# PV_MCU_IO.net
KiCad netlist of a schematic drawn in Altium Designer
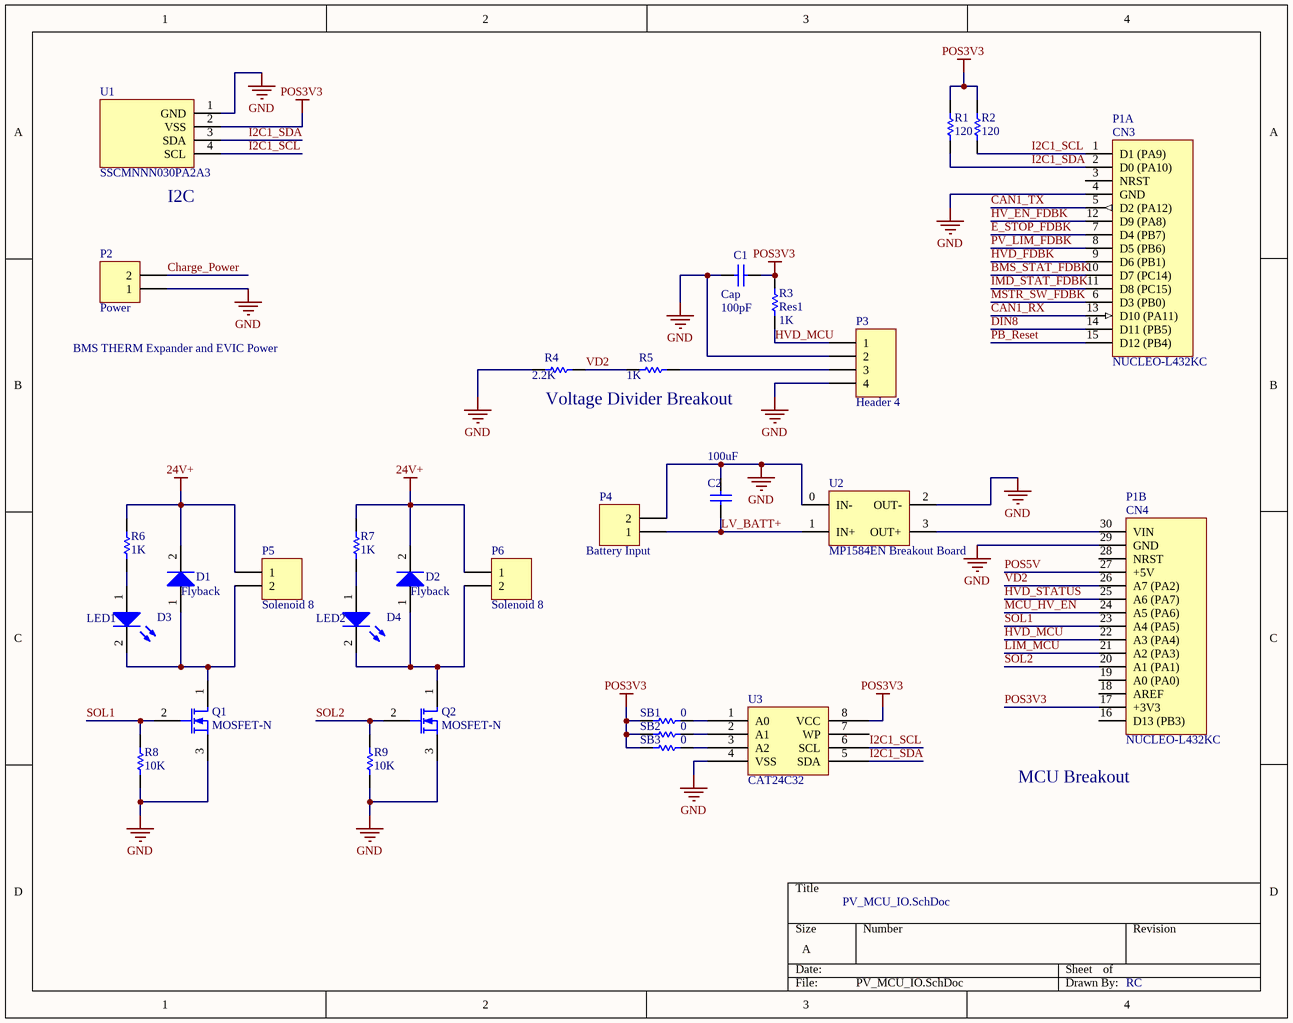
[diagram p0: PV_MCU_IO.SchDoc]

(export (version "E")
  (design (tool "Eeschema 10.0.6"))
  (components
    (comp (ref "C1")
      (value "Cap")
      (footprint "1206")
      (description "Capacitor")
      (fields (field (name "ALTIUM_VALUE") "100pF") (field (name "PUBLISHER") "Altium Limited"))
      (libsource (lib "Miscellaneous Devices") (part "Cap"))
    )
    (comp (ref "C2")
      (value "100uF")
      (footprint "CAPR5-4X5")
      (description "Capacitor")
      (fields (field (name "Comment") "Cap") (field (name "PUBLISHER") "Altium Limited"))
      (libsource (lib "Miscellaneous Devices") (part "Cap"))
    )
    (comp (ref "D1")
      (value "Flyback")
      (footprint "1N4007")
      (description "Default Diode")
      (fields (field (name "PUBLISHER") "Altium Limited"))
      (libsource (lib "Miscellaneous Devices") (part "Diode"))
    )
    (comp (ref "D2")
      (value "Flyback")
      (footprint "1N4007")
      (description "Default Diode")
      (fields (field (name "PUBLISHER") "Altium Limited"))
      (libsource (lib "Miscellaneous Devices") (part "Diode"))
    )
    (comp (ref "D3")
      (value "LED1")
      (footprint "1206 LED")
      (description "Typical RED, GREEN, YELLOW, AMBER GaAs LED")
      (fields (field (name "PUBLISHER") "Altium Limited"))
      (libsource (lib "Miscellaneous Devices") (part "LED2"))
    )
    (comp (ref "D4")
      (value "LED2")
      (footprint "1206 LED")
      (description "Typical RED, GREEN, YELLOW, AMBER GaAs LED")
      (fields (field (name "PUBLISHER") "Altium Limited"))
      (libsource (lib "Miscellaneous Devices") (part "LED2"))
    )
    (comp (ref "P1")
      (value "NUCLEO-L432KC")
      (footprint "NUCLEO-32")
      (description "STM32L432KC Development Board")
      (libsource (lib "") (part "NUCLEO-L432KC_1"))
    )
    (comp (ref "P2")
      (value "Power")
      (footprint "2POS TERM BLOCK")
      (description "Header, 2-Pin")
      (fields (field (name "PUBLISHER") "Altium Limited"))
      (libsource (lib "") (part "Header 2_1"))
    )
    (comp (ref "P3")
      (value "Header 4")
      (footprint "4POS TERM BLOCK")
      (description "Header, 4-Pin")
      (fields (field (name "PUBLISHER") "Altium Limited"))
      (libsource (lib "Miscellaneous Connectors") (part "Header 4"))
    )
    (comp (ref "P4")
      (value "Battery Input")
      (footprint "2POS TERM BLOCK")
      (description "Header, 2-Pin")
      (fields (field (name "PUBLISHER") "Altium Limited"))
      (libsource (lib "") (part "Header 2_1"))
    )
    (comp (ref "P5")
      (value "Solenoid 8")
      (footprint "2POS TERM BLOCK")
      (description "Header, 2-Pin")
      (fields (field (name "PUBLISHER") "Altium Limited"))
      (libsource (lib "Miscellaneous Connectors") (part "Header 2"))
    )
    (comp (ref "P6")
      (value "Solenoid 8")
      (footprint "2POS TERM BLOCK")
      (description "Header, 2-Pin")
      (fields (field (name "PUBLISHER") "Altium Limited"))
      (libsource (lib "Miscellaneous Connectors") (part "Header 2"))
    )
    (comp (ref "Q1")
      (value "MOSFET-N")
      (footprint "SOT-23-3")
      (description "N-Channel MOSFET")
      (fields (field (name "PUBLISHER") "Altium Limited"))
      (libsource (lib "Miscellaneous Devices") (part "MOSFET-N"))
    )
    (comp (ref "Q2")
      (value "MOSFET-N")
      (footprint "SOT-23-3")
      (description "N-Channel MOSFET")
      (fields (field (name "PUBLISHER") "Altium Limited"))
      (libsource (lib "Miscellaneous Devices") (part "MOSFET-N"))
    )
    (comp (ref "R1")
      (value "120")
      (footprint "1206")
      (description "Resistor")
      (fields (field (name "Comment") "Res1") (field (name "PUBLISHER") "Altium Limited"))
      (libsource (lib "Miscellaneous Devices") (part "Res1"))
    )
    (comp (ref "R2")
      (value "120")
      (footprint "1206")
      (description "Resistor")
      (fields (field (name "Comment") "Res1") (field (name "PUBLISHER") "Altium Limited"))
      (libsource (lib "Miscellaneous Devices") (part "Res1"))
    )
    (comp (ref "R3")
      (value "Res1")
      (footprint "1206")
      (description "Resistor")
      (fields (field (name "ALTIUM_VALUE") "1K") (field (name "PUBLISHER") "Altium Limited"))
      (libsource (lib "Miscellaneous Devices") (part "Res1"))
    )
    (comp (ref "R4")
      (value "2.2K")
      (footprint "1206")
      (description "Resistor")
      (fields (field (name "Comment") "Res1") (field (name "PUBLISHER") "Altium Limited"))
      (libsource (lib "Miscellaneous Devices") (part "Res1"))
    )
    (comp (ref "R5")
      (value "1K")
      (footprint "1206")
      (description "Resistor")
      (fields (field (name "Comment") "Res1") (field (name "PUBLISHER") "Altium Limited"))
      (libsource (lib "Miscellaneous Devices") (part "Res1"))
    )
    (comp (ref "R6")
      (value "1K")
      (footprint "1206")
      (description "Resistor")
      (fields (field (name "Comment") "Res1") (field (name "PUBLISHER") "Altium Limited"))
      (libsource (lib "Miscellaneous Devices") (part "Res1"))
    )
    (comp (ref "R7")
      (value "1K")
      (footprint "1206")
      (description "Resistor")
      (fields (field (name "Comment") "Res1") (field (name "PUBLISHER") "Altium Limited"))
      (libsource (lib "Miscellaneous Devices") (part "Res1"))
    )
    (comp (ref "R8")
      (value "10K")
      (footprint "1206")
      (description "Resistor")
      (fields (field (name "Comment") "Res1") (field (name "PUBLISHER") "Altium Limited"))
      (libsource (lib "Miscellaneous Devices") (part "Res1"))
    )
    (comp (ref "R9")
      (value "10K")
      (footprint "1206")
      (description "Resistor")
      (fields (field (name "Comment") "Res1") (field (name "PUBLISHER") "Altium Limited"))
      (libsource (lib "Miscellaneous Devices") (part "Res1"))
    )
    (comp (ref "SB1")
      (value "0")
      (footprint "6-0805_M")
      (description "Resistor")
      (fields (field (name "Comment") "Res1") (field (name "PUBLISHER") "Altium Limited"))
      (libsource (lib "Miscellaneous Devices") (part "Res1"))
    )
    (comp (ref "SB2")
      (value "0")
      (footprint "6-0805_M")
      (description "Resistor")
      (fields (field (name "Comment") "Res1") (field (name "PUBLISHER") "Altium Limited"))
      (libsource (lib "Miscellaneous Devices") (part "Res1"))
    )
    (comp (ref "SB3")
      (value "0")
      (footprint "6-0805_M")
      (description "Resistor")
      (fields (field (name "Comment") "Res1") (field (name "PUBLISHER") "Altium Limited"))
      (libsource (lib "Miscellaneous Devices") (part "Res1"))
    )
    (comp (ref "U1")
      (value "SSCMNNN030PA2A3")
      (footprint "8-SMT")
      (description "Honeywell Digital Pressure Sensor")
      (libsource (lib "ic") (part "SSCMNNN030PA2A3"))
    )
    (comp (ref "U2")
      (value "MP1584EN Breakout Board")
      (footprint "MP1584EN Breakout")
      (description "Buck Converter")
      (libsource (lib "ic") (part "MP1584EN Breakout Board"))
    )
    (comp (ref "U3")
      (value "CAT24C32")
      (footprint "SO8_N")
      (description "I2C EEPROM")
      (libsource (lib "ic") (part "CAT24C32"))
    )
  )
  (nets
    (net (code "1") (name "/BMS_STAT_FDBK") (class "Default")
      (node (ref "P1") (pin "10") (pinfunction "D7_(PC14)_10") (pintype "passive"))
    )
    (net (code "2") (name "/CAN1_RX") (class "Default")
      (node (ref "P1") (pin "13") (pinfunction "D10_(PA11)_13") (pintype "input"))
    )
    (net (code "3") (name "/CAN1_TX") (class "Default")
      (node (ref "P1") (pin "5") (pinfunction "D2_(PA12)_5") (pintype "output"))
    )
    (net (code "4") (name "/Charge_Power") (class "Default")
      (node (ref "P2") (pin "2") (pinfunction "2_2") (pintype "passive"))
    )
    (net (code "5") (name "/DIN8") (class "Default")
      (node (ref "P1") (pin "14") (pinfunction "D11_(PB5)_14") (pintype "passive"))
    )
    (net (code "6") (name "/E_STOP_FDBK") (class "Default")
      (node (ref "P1") (pin "7") (pinfunction "D4_(PB7)_7") (pintype "passive"))
    )
    (net (code "7") (name "/HVD_FDBK") (class "Default")
      (node (ref "P1") (pin "9") (pinfunction "D6_(PB1)_9") (pintype "passive"))
    )
    (net (code "8") (name "/HVD_MCU") (class "Default")
      (node (ref "P1") (pin "22") (pinfunction "A3_(PA4)_22") (pintype "passive"))
      (node (ref "P3") (pin "1") (pinfunction "1_1") (pintype "passive"))
      (node (ref "R3") (pin "1") (pinfunction "1_1") (pintype "passive"))
    )
    (net (code "9") (name "/HVD_STATUS") (class "Default")
      (node (ref "P1") (pin "25") (pinfunction "A6_(PA7)_25") (pintype "passive"))
    )
    (net (code "10") (name "/HV_EN_FDBK") (class "Default")
      (node (ref "P1") (pin "12") (pinfunction "D9_(PA8)_12") (pintype "passive"))
    )
    (net (code "11") (name "/I2C1_SCL") (class "Default")
      (node (ref "P1") (pin "1") (pinfunction "D1_(PA9)_1") (pintype "passive"))
      (node (ref "R2") (pin "1") (pinfunction "1_1") (pintype "passive"))
      (node (ref "U1") (pin "4") (pinfunction "SCL_4") (pintype "passive"))
      (node (ref "U3") (pin "6") (pinfunction "SCL_6") (pintype "passive"))
    )
    (net (code "12") (name "/I2C1_SDA") (class "Default")
      (node (ref "P1") (pin "2") (pinfunction "D0_(PA10)_2") (pintype "passive"))
      (node (ref "R1") (pin "1") (pinfunction "1_1") (pintype "passive"))
      (node (ref "U1") (pin "3") (pinfunction "SDA_3") (pintype "passive"))
      (node (ref "U3") (pin "5") (pinfunction "SDA_5") (pintype "passive"))
    )
    (net (code "13") (name "/IMD_STAT_FDBK") (class "Default")
      (node (ref "P1") (pin "11") (pinfunction "D8_(PC15)_11") (pintype "passive"))
    )
    (net (code "14") (name "/LIM_MCU") (class "Default")
      (node (ref "P1") (pin "21") (pinfunction "A2_(PA3)_21") (pintype "passive"))
    )
    (net (code "15") (name "/LV_BATT+") (class "Default")
      (node (ref "C2") (pin "1") (pinfunction "1_1") (pintype "passive"))
      (node (ref "P4") (pin "1") (pinfunction "1_1") (pintype "passive"))
      (node (ref "U2") (pin "1") (pinfunction "IN+_1") (pintype "power_in"))
    )
    (net (code "16") (name "/MCU_HV_EN") (class "Default")
      (node (ref "P1") (pin "24") (pinfunction "A5_(PA6)_24") (pintype "passive"))
    )
    (net (code "17") (name "/MSTR_SW_FDBK") (class "Default")
      (node (ref "P1") (pin "6") (pinfunction "D3_(PB0)_6") (pintype "passive"))
    )
    (net (code "18") (name "/PB_Reset") (class "Default")
      (node (ref "P1") (pin "15") (pinfunction "D12_(PB4)_15") (pintype "passive"))
    )
    (net (code "19") (name "/POS5V") (class "Default")
      (node (ref "P1") (pin "27") (pinfunction "+5V_27") (pintype "passive"))
    )
    (net (code "20") (name "/PV_LIM_FDBK") (class "Default")
      (node (ref "P1") (pin "8") (pinfunction "D5_(PB6)_8") (pintype "passive"))
    )
    (net (code "21") (name "/SOL1") (class "Default")
      (node (ref "P1") (pin "23") (pinfunction "A4_(PA5)_23") (pintype "passive"))
      (node (ref "Q1") (pin "2") (pinfunction "G_2") (pintype "passive"))
      (node (ref "R8") (pin "2") (pinfunction "2_2") (pintype "passive"))
    )
    (net (code "22") (name "/SOL2") (class "Default")
      (node (ref "P1") (pin "20") (pinfunction "A1_(PA1)_20") (pintype "passive"))
      (node (ref "Q2") (pin "2") (pinfunction "G_2") (pintype "passive"))
      (node (ref "R9") (pin "2") (pinfunction "2_2") (pintype "passive"))
    )
    (net (code "23") (name "/VD2") (class "Default")
      (node (ref "P1") (pin "26") (pinfunction "A7_(PA2)_26") (pintype "passive"))
      (node (ref "R4") (pin "2") (pinfunction "2_2") (pintype "passive"))
      (node (ref "R5") (pin "1") (pinfunction "1_1") (pintype "passive"))
    )
    (net (code "24") (name "24V+") (class "Default")
      (node (ref "D1") (pin "2") (pinfunction "K_2") (pintype "passive"))
      (node (ref "D2") (pin "2") (pinfunction "K_2") (pintype "passive"))
      (node (ref "P5") (pin "1") (pinfunction "1_1") (pintype "passive"))
      (node (ref "P6") (pin "1") (pinfunction "1_1") (pintype "passive"))
      (node (ref "R6") (pin "2") (pinfunction "2_2") (pintype "passive"))
      (node (ref "R7") (pin "2") (pinfunction "2_2") (pintype "passive"))
    )
    (net (code "25") (name "GND") (class "Default")
      (node (ref "C1") (pin "2") (pinfunction "2_2") (pintype "passive"))
      (node (ref "C2") (pin "2") (pinfunction "2_2") (pintype "passive"))
      (node (ref "P1") (pin "29") (pinfunction "GND_29") (pintype "passive"))
      (node (ref "P1") (pin "4") (pinfunction "GND_4") (pintype "passive"))
      (node (ref "P2") (pin "1") (pinfunction "1_1") (pintype "passive"))
      (node (ref "P3") (pin "2") (pinfunction "2_2") (pintype "passive"))
      (node (ref "P3") (pin "4") (pinfunction "4_4") (pintype "passive"))
      (node (ref "P4") (pin "2") (pinfunction "2_2") (pintype "passive"))
      (node (ref "Q1") (pin "3") (pinfunction "S_3") (pintype "passive"))
      (node (ref "Q2") (pin "3") (pinfunction "S_3") (pintype "passive"))
      (node (ref "R4") (pin "1") (pinfunction "1_1") (pintype "passive"))
      (node (ref "R8") (pin "1") (pinfunction "1_1") (pintype "passive"))
      (node (ref "R9") (pin "1") (pinfunction "1_1") (pintype "passive"))
      (node (ref "U1") (pin "1") (pinfunction "GND_1") (pintype "passive"))
      (node (ref "U2") (pin "0") (pinfunction "IN-_0") (pintype "passive"))
      (node (ref "U2") (pin "2") (pinfunction "OUT-_2") (pintype "passive"))
      (node (ref "U3") (pin "4") (pinfunction "VSS_4") (pintype "passive"))
    )
    (net (code "26") (name "Net-(D1-A)") (class "Default")
      (node (ref "D1") (pin "1") (pinfunction "A_1") (pintype "passive"))
      (node (ref "D3") (pin "2") (pinfunction "K_2") (pintype "passive"))
      (node (ref "P5") (pin "2") (pinfunction "2_2") (pintype "passive"))
      (node (ref "Q1") (pin "1") (pinfunction "D_1") (pintype "passive"))
    )
    (net (code "27") (name "Net-(D2-A)") (class "Default")
      (node (ref "D2") (pin "1") (pinfunction "A_1") (pintype "passive"))
      (node (ref "D4") (pin "2") (pinfunction "K_2") (pintype "passive"))
      (node (ref "P6") (pin "2") (pinfunction "2_2") (pintype "passive"))
      (node (ref "Q2") (pin "1") (pinfunction "D_1") (pintype "passive"))
    )
    (net (code "28") (name "Net-(D3-A)") (class "Default")
      (node (ref "D3") (pin "1") (pinfunction "A_1") (pintype "passive"))
      (node (ref "R6") (pin "1") (pinfunction "1_1") (pintype "passive"))
    )
    (net (code "29") (name "Net-(D4-A)") (class "Default")
      (node (ref "D4") (pin "1") (pinfunction "A_1") (pintype "passive"))
      (node (ref "R7") (pin "1") (pinfunction "1_1") (pintype "passive"))
    )
    (net (code "30") (name "Net-(P1B-VIN)") (class "Default")
      (node (ref "P1") (pin "30") (pinfunction "VIN_30") (pintype "passive"))
      (node (ref "U2") (pin "3") (pinfunction "OUT+_3") (pintype "power_in"))
    )
    (net (code "31") (name "Net-(P3-Pad3)") (class "Default")
      (node (ref "P3") (pin "3") (pinfunction "3_3") (pintype "passive"))
      (node (ref "R5") (pin "2") (pinfunction "2_2") (pintype "passive"))
    )
    (net (code "32") (name "Net-(U3-A0)") (class "Default")
      (node (ref "SB1") (pin "1") (pinfunction "1_1") (pintype "passive"))
      (node (ref "U3") (pin "1") (pinfunction "A0_1") (pintype "passive"))
    )
    (net (code "33") (name "Net-(U3-A1)") (class "Default")
      (node (ref "SB2") (pin "1") (pinfunction "1_1") (pintype "passive"))
      (node (ref "U3") (pin "2") (pinfunction "A1_2") (pintype "passive"))
    )
    (net (code "34") (name "Net-(U3-A2)") (class "Default")
      (node (ref "SB3") (pin "1") (pinfunction "1_1") (pintype "passive"))
      (node (ref "U3") (pin "3") (pinfunction "A2_3") (pintype "passive"))
    )
    (net (code "35") (name "POS3V3") (class "Default")
      (node (ref "C1") (pin "1") (pinfunction "1_1") (pintype "passive"))
      (node (ref "P1") (pin "17") (pinfunction "+3V3_17") (pintype "passive"))
      (node (ref "R1") (pin "2") (pinfunction "2_2") (pintype "passive"))
      (node (ref "R2") (pin "2") (pinfunction "2_2") (pintype "passive"))
      (node (ref "R3") (pin "2") (pinfunction "2_2") (pintype "passive"))
      (node (ref "SB1") (pin "2") (pinfunction "2_2") (pintype "passive"))
      (node (ref "SB2") (pin "2") (pinfunction "2_2") (pintype "passive"))
      (node (ref "SB3") (pin "2") (pinfunction "2_2") (pintype "passive"))
      (node (ref "U1") (pin "2") (pinfunction "VSS_2") (pintype "power_in"))
      (node (ref "U3") (pin "8") (pinfunction "VCC_8") (pintype "power_in"))
    )
    (net (code "36") (name "unconnected-(P1A-NRST-Pad3)") (class "Default")
      (node (ref "P1") (pin "3") (pinfunction "NRST_3") (pintype "passive"))
    )
    (net (code "37") (name "unconnected-(P1B-A0_(PA0)-Pad19)") (class "Default")
      (node (ref "P1") (pin "19") (pinfunction "A0_(PA0)_19") (pintype "passive"))
    )
    (net (code "38") (name "unconnected-(P1B-AREF-Pad18)") (class "Default")
      (node (ref "P1") (pin "18") (pinfunction "AREF_18") (pintype "passive"))
    )
    (net (code "39") (name "unconnected-(P1B-D13_(PB3)-Pad16)") (class "Default")
      (node (ref "P1") (pin "16") (pinfunction "D13_(PB3)_16") (pintype "passive"))
    )
    (net (code "40") (name "unconnected-(P1B-NRST-Pad28)") (class "Default")
      (node (ref "P1") (pin "28") (pinfunction "NRST_28") (pintype "passive"))
    )
    (net (code "41") (name "unconnected-(U3-WP-Pad7)") (class "Default")
      (node (ref "U3") (pin "7") (pinfunction "WP_7") (pintype "passive"))
    )
  )
)
